# DSPIC33_Board_2020_09_23_A.net
KiCad netlist of a schematic drawn in EAGLE
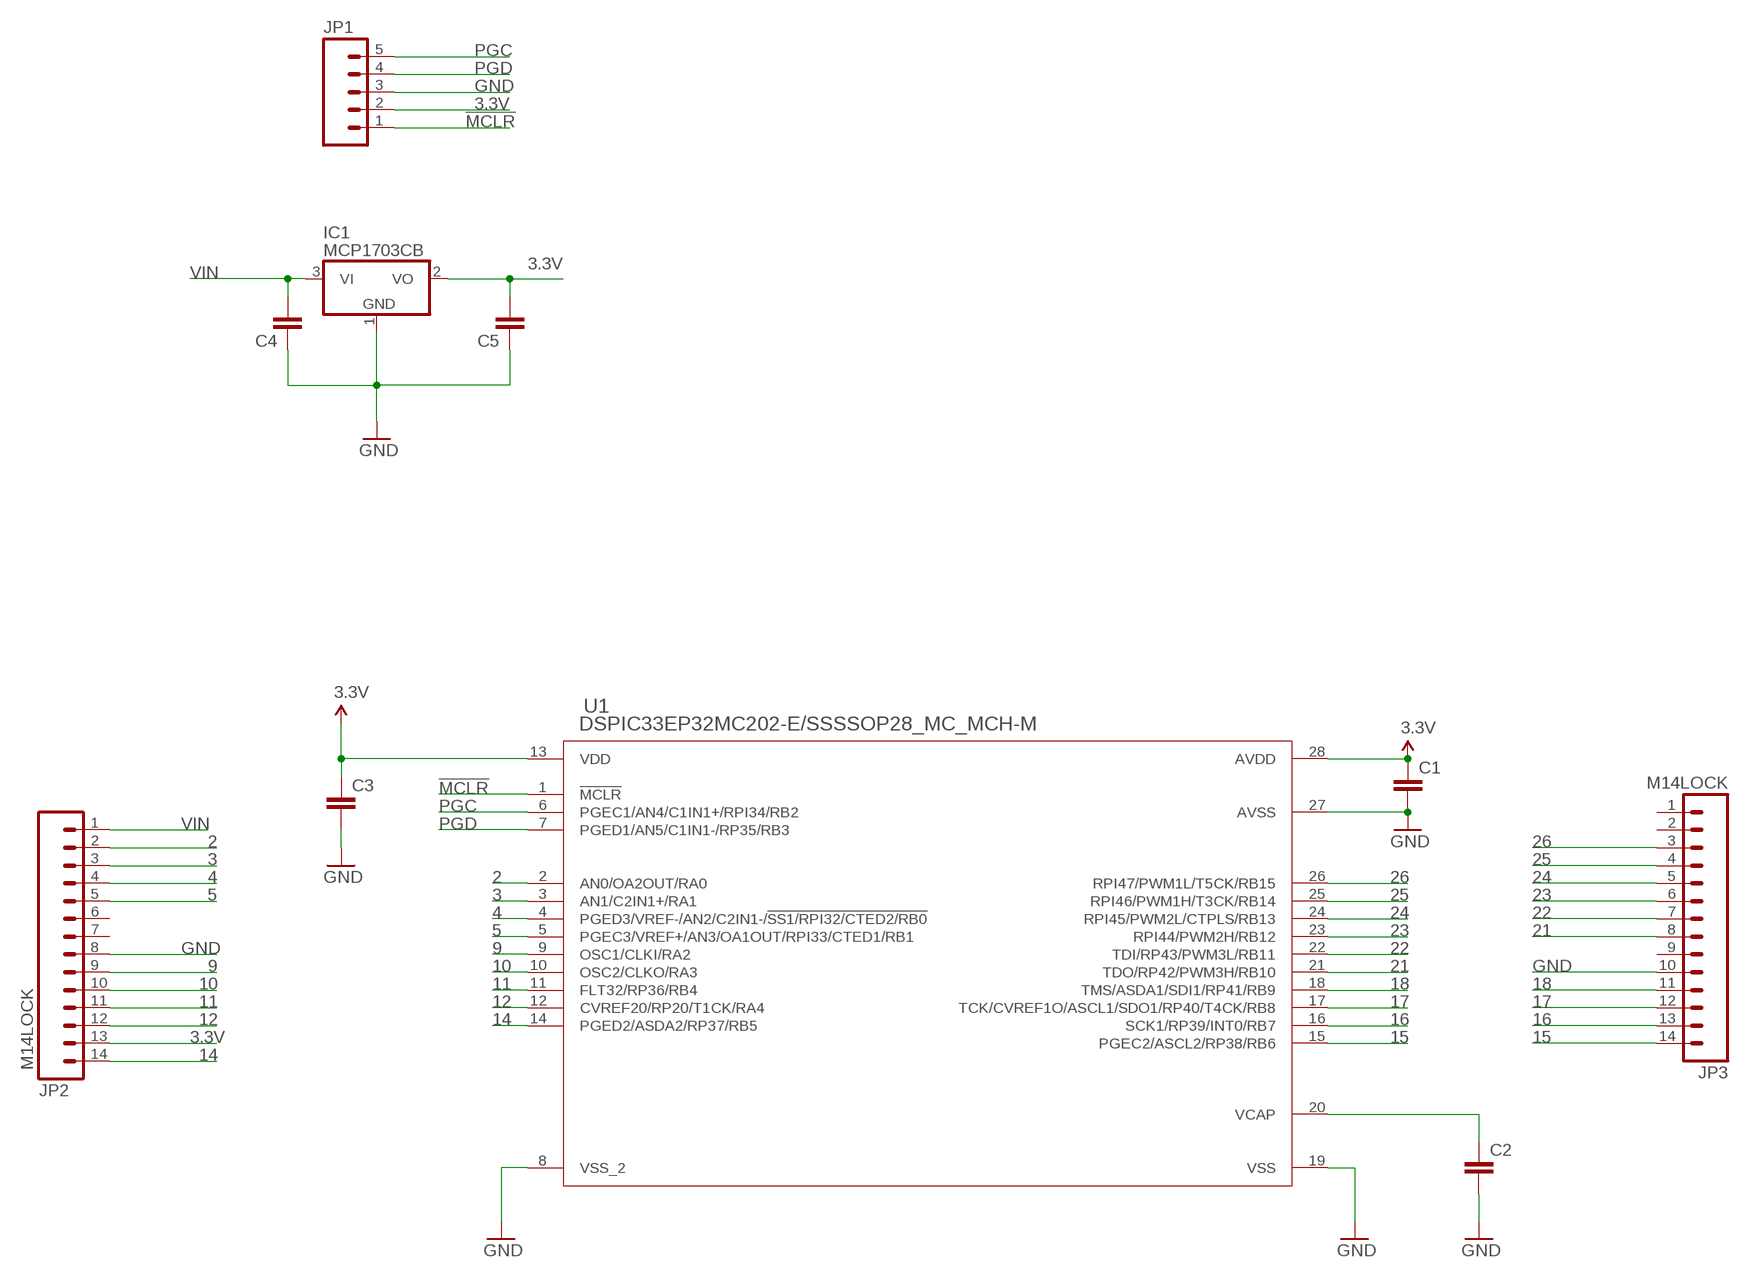
[diagram p0: schematic, sheet 1]

(export (version "E")
  (design (tool "Eeschema 10.0.6"))
  (components
    (comp (ref "C1")
      (value "CAP1206")
      (footprint "eagle-import:1206")
      (libsource (lib "eagle-import") (part "CAP1206"))
    )
    (comp (ref "C2")
      (value "CAP1206")
      (footprint "eagle-import:1206")
      (libsource (lib "eagle-import") (part "CAP1206"))
    )
    (comp (ref "C3")
      (value "CAP1206")
      (footprint "eagle-import:1206")
      (libsource (lib "eagle-import") (part "CAP1206"))
    )
    (comp (ref "C4")
      (value "CAP1206")
      (footprint "eagle-import:1206")
      (libsource (lib "eagle-import") (part "CAP1206"))
    )
    (comp (ref "C5")
      (value "CAP1206")
      (footprint "eagle-import:1206")
      (libsource (lib "eagle-import") (part "CAP1206"))
    )
    (comp (ref "IC1")
      (value "MCP1703CB")
      (footprint "eagle-import:SOT23")
      (libsource (lib "eagle-import") (part "MCP1703CB"))
    )
    (comp (ref "JP1")
      (value "M05LOCK")
      (footprint "eagle-import:1X05_LOCK")
      (libsource (lib "eagle-import") (part "M05LOCK"))
    )
    (comp (ref "JP2")
      (value "M14LOCK")
      (footprint "eagle-import:1X14_LOCK")
      (libsource (lib "eagle-import") (part "M14LOCK"))
    )
    (comp (ref "JP3")
      (value "M14LOCK")
      (footprint "eagle-import:1X14_LOCK")
      (libsource (lib "eagle-import") (part "M14LOCK"))
    )
    (comp (ref "U1")
      (value "DSPIC33EP32MC202-E/SSSSOP28_MC_MCH-M")
      (footprint "eagle-import:SSOP28_MC_MCH-M")
      (fields
        (field (name "MANUFACTURER_PART_NUMBER") "DSPIC33EP32MC202-E/SS")
        (field (name "COPYRIGHT") "Copyright (C) 2018 Accelerated Designs. All rights reserved")
      )
      (libsource (lib "eagle-import") (part "DSPIC33EP32MC202-E/SSSSOP28_MC_MCH-M"))
    )
  )
  (nets
    (net (code "1") (name "/2") (class "Default")
      (node (ref "JP2") (pin "2") (pinfunction "2_2") (pintype "passive"))
      (node (ref "U1") (pin "2") (pinfunction "AN0/OA2OUT/RA0_2") (pintype "bidirectional"))
    )
    (net (code "2") (name "/3") (class "Default")
      (node (ref "JP2") (pin "3") (pinfunction "3_3") (pintype "passive"))
      (node (ref "U1") (pin "3") (pinfunction "AN1/C2IN1+/RA1_3") (pintype "bidirectional"))
    )
    (net (code "3") (name "/4") (class "Default")
      (node (ref "JP2") (pin "4") (pinfunction "4_4") (pintype "passive"))
      (node (ref "U1") (pin "4") (pinfunction "PGED3/VREF-/AN2/C2IN1-/~{SS1/RPI32/CTED2/RB0}_4") (pintype "bidirectional"))
    )
    (net (code "4") (name "/5") (class "Default")
      (node (ref "JP2") (pin "5") (pinfunction "5_5") (pintype "passive"))
      (node (ref "U1") (pin "5") (pinfunction "PGEC3/VREF+/AN3/OA1OUT/RPI33/CTED1/RB1_5") (pintype "bidirectional"))
    )
    (net (code "5") (name "/9") (class "Default")
      (node (ref "JP2") (pin "9") (pinfunction "9_9") (pintype "passive"))
      (node (ref "U1") (pin "9") (pinfunction "OSC1/CLKI/RA2_9") (pintype "bidirectional"))
    )
    (net (code "6") (name "/10") (class "Default")
      (node (ref "JP2") (pin "10") (pinfunction "10_10") (pintype "passive"))
      (node (ref "U1") (pin "10") (pinfunction "OSC2/CLKO/RA3_10") (pintype "bidirectional"))
    )
    (net (code "7") (name "/11") (class "Default")
      (node (ref "JP2") (pin "11") (pinfunction "11_11") (pintype "passive"))
      (node (ref "U1") (pin "11") (pinfunction "FLT32/RP36/RB4_11") (pintype "bidirectional"))
    )
    (net (code "8") (name "/12") (class "Default")
      (node (ref "JP2") (pin "12") (pinfunction "12_12") (pintype "passive"))
      (node (ref "U1") (pin "12") (pinfunction "CVREF20/RP20/T1CK/RA4_12") (pintype "bidirectional"))
    )
    (net (code "9") (name "/14") (class "Default")
      (node (ref "JP2") (pin "14") (pinfunction "14_14") (pintype "passive"))
      (node (ref "U1") (pin "14") (pinfunction "PGED2/ASDA2/RP37/RB5_14") (pintype "bidirectional"))
    )
    (net (code "10") (name "/15") (class "Default")
      (node (ref "JP3") (pin "14") (pinfunction "14_14") (pintype "passive"))
      (node (ref "U1") (pin "15") (pinfunction "PGEC2/ASCL2/RP38/RB6_15") (pintype "bidirectional"))
    )
    (net (code "11") (name "/16") (class "Default")
      (node (ref "JP3") (pin "13") (pinfunction "13_13") (pintype "passive"))
      (node (ref "U1") (pin "16") (pinfunction "SCK1/RP39/INT0/RB7_16") (pintype "bidirectional"))
    )
    (net (code "12") (name "/17") (class "Default")
      (node (ref "JP3") (pin "12") (pinfunction "12_12") (pintype "passive"))
      (node (ref "U1") (pin "17") (pinfunction "TCK/CVREF1O/ASCL1/SDO1/RP40/T4CK/RB8_17") (pintype "bidirectional"))
    )
    (net (code "13") (name "/18") (class "Default")
      (node (ref "JP3") (pin "11") (pinfunction "11_11") (pintype "passive"))
      (node (ref "U1") (pin "18") (pinfunction "TMS/ASDA1/SDI1/RP41/RB9_18") (pintype "bidirectional"))
    )
    (net (code "14") (name "/21") (class "Default")
      (node (ref "JP3") (pin "8") (pinfunction "8_8") (pintype "passive"))
      (node (ref "U1") (pin "21") (pinfunction "TDO/RP42/PWM3H/RB10_21") (pintype "bidirectional"))
    )
    (net (code "15") (name "/22") (class "Default")
      (node (ref "JP3") (pin "7") (pinfunction "7_7") (pintype "passive"))
      (node (ref "U1") (pin "22") (pinfunction "TDI/RP43/PWM3L/RB11_22") (pintype "bidirectional"))
    )
    (net (code "16") (name "/23") (class "Default")
      (node (ref "JP3") (pin "6") (pinfunction "6_6") (pintype "passive"))
      (node (ref "U1") (pin "23") (pinfunction "RPI44/PWM2H/RB12_23") (pintype "bidirectional"))
    )
    (net (code "17") (name "/24") (class "Default")
      (node (ref "JP3") (pin "5") (pinfunction "5_5") (pintype "passive"))
      (node (ref "U1") (pin "24") (pinfunction "RPI45/PWM2L/CTPLS/RB13_24") (pintype "bidirectional"))
    )
    (net (code "18") (name "/25") (class "Default")
      (node (ref "JP3") (pin "4") (pinfunction "4_4") (pintype "passive"))
      (node (ref "U1") (pin "25") (pinfunction "RPI46/PWM1H/T3CK/RB14_25") (pintype "bidirectional"))
    )
    (net (code "19") (name "/26") (class "Default")
      (node (ref "JP3") (pin "3") (pinfunction "3_3") (pintype "passive"))
      (node (ref "U1") (pin "26") (pinfunction "RPI47/PWM1L/T5CK/RB15_26") (pintype "bidirectional"))
    )
    (net (code "20") (name "/PGC") (class "Default")
      (node (ref "JP1") (pin "5") (pinfunction "5_5") (pintype "passive"))
      (node (ref "U1") (pin "6") (pinfunction "PGEC1/AN4/C1IN1+/RPI34/RB2_6") (pintype "bidirectional"))
    )
    (net (code "21") (name "/PGD") (class "Default")
      (node (ref "JP1") (pin "4") (pinfunction "4_4") (pintype "passive"))
      (node (ref "U1") (pin "7") (pinfunction "PGED1/AN5/C1IN1-/RP35/RB3_7") (pintype "bidirectional"))
    )
    (net (code "22") (name "/VIN") (class "Default")
      (node (ref "C4") (pin "2") (pinfunction "2_2") (pintype "passive"))
      (node (ref "IC1") (pin "3") (pinfunction "VI_3") (pintype "input"))
      (node (ref "JP2") (pin "1") (pinfunction "1_1") (pintype "passive"))
    )
    (net (code "23") (name "/~{MCLR}") (class "Default")
      (node (ref "JP1") (pin "1") (pinfunction "1_1") (pintype "passive"))
      (node (ref "U1") (pin "1") (pinfunction "~{MCLR}_1") (pintype "bidirectional"))
    )
    (net (code "24") (name "3.3V") (class "Default")
      (node (ref "C1") (pin "1") (pinfunction "1_1") (pintype "passive"))
      (node (ref "C3") (pin "1") (pinfunction "1_1") (pintype "passive"))
      (node (ref "C5") (pin "2") (pinfunction "2_2") (pintype "passive"))
      (node (ref "IC1") (pin "2") (pinfunction "VO_2") (pintype "passive"))
      (node (ref "JP1") (pin "2") (pinfunction "2_2") (pintype "passive"))
      (node (ref "JP2") (pin "13") (pinfunction "13_13") (pintype "passive"))
      (node (ref "U1") (pin "13") (pinfunction "VDD_13") (pintype "power_in"))
      (node (ref "U1") (pin "28") (pinfunction "AVDD_28") (pintype "power_in"))
    )
    (net (code "25") (name "GND") (class "Default")
      (node (ref "C1") (pin "2") (pinfunction "2_2") (pintype "passive"))
      (node (ref "C2") (pin "1") (pinfunction "1_1") (pintype "passive"))
      (node (ref "C3") (pin "2") (pinfunction "2_2") (pintype "passive"))
      (node (ref "C4") (pin "1") (pinfunction "1_1") (pintype "passive"))
      (node (ref "C5") (pin "1") (pinfunction "1_1") (pintype "passive"))
      (node (ref "IC1") (pin "1") (pinfunction "GND_1") (pintype "passive"))
      (node (ref "JP1") (pin "3") (pinfunction "3_3") (pintype "passive"))
      (node (ref "JP2") (pin "8") (pinfunction "8_8") (pintype "passive"))
      (node (ref "JP3") (pin "10") (pinfunction "10_10") (pintype "passive"))
      (node (ref "U1") (pin "19") (pinfunction "VSS_19") (pintype "power_in"))
      (node (ref "U1") (pin "27") (pinfunction "AVSS_27") (pintype "power_in"))
      (node (ref "U1") (pin "8") (pinfunction "VSS_2_8") (pintype "power_in"))
    )
    (net (code "26") (name "Net-(U1-VCAP)") (class "Default")
      (node (ref "C2") (pin "2") (pinfunction "2_2") (pintype "passive"))
      (node (ref "U1") (pin "20") (pinfunction "VCAP_20") (pintype "power_in"))
    )
    (net (code "27") (name "unconnected-(JP2-Pad6)") (class "Default")
      (node (ref "JP2") (pin "6") (pinfunction "6_6") (pintype "passive"))
    )
    (net (code "28") (name "unconnected-(JP2-Pad7)") (class "Default")
      (node (ref "JP2") (pin "7") (pinfunction "7_7") (pintype "passive"))
    )
    (net (code "29") (name "unconnected-(JP3-Pad1)") (class "Default")
      (node (ref "JP3") (pin "1") (pinfunction "1_1") (pintype "passive"))
    )
    (net (code "30") (name "unconnected-(JP3-Pad2)") (class "Default")
      (node (ref "JP3") (pin "2") (pinfunction "2_2") (pintype "passive"))
    )
    (net (code "31") (name "unconnected-(JP3-Pad9)") (class "Default")
      (node (ref "JP3") (pin "9") (pinfunction "9_9") (pintype "passive"))
    )
  )
)
